# inputmgr.net
KiCad netlist of a schematic drawn in EAGLE
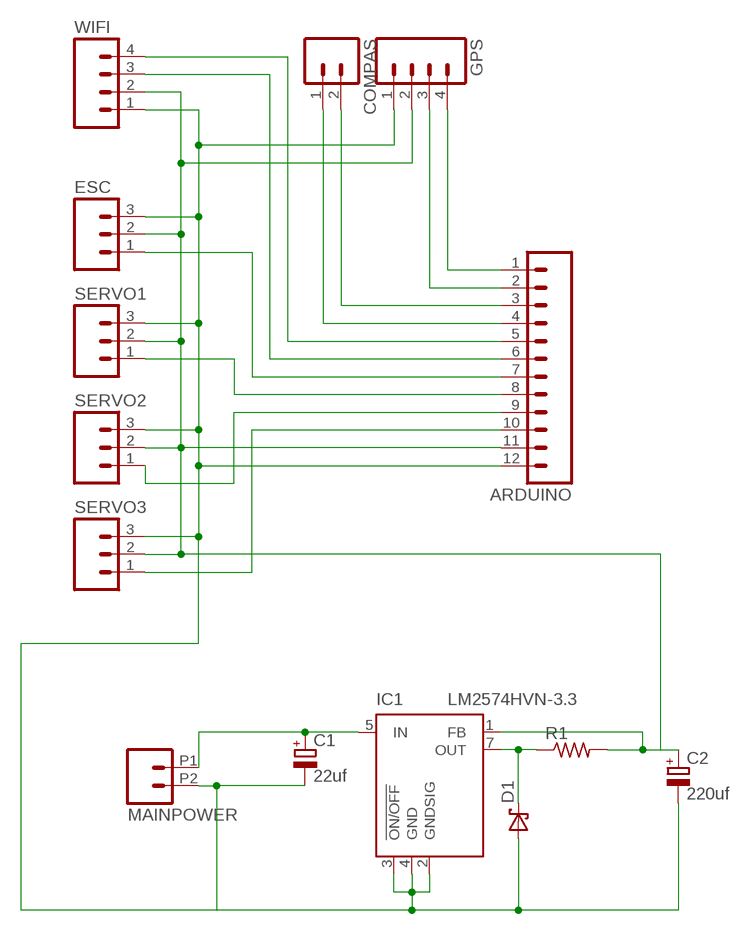
[diagram p0: schematic, sheet 1]

(export (version "E")
  (design (tool "Eeschema 10.0.6"))
  (components
    (comp (ref "ARDUINO")
      (value "M12PTH")
      (footprint "eagle-import:1X12")
      (libsource (lib "eagle-import") (part "M12PTH"))
    )
    (comp (ref "C1")
      (value "22uf")
      (footprint "eagle-import:E2,5-6")
      (libsource (lib "eagle-import") (part "CPOL-EUE2.5-6"))
    )
    (comp (ref "C2")
      (value "220uf")
      (footprint "eagle-import:E2,5-6")
      (libsource (lib "eagle-import") (part "CPOL-EUE2.5-6"))
    )
    (comp (ref "COMPAS")
      (value "M02PTH")
      (footprint "eagle-import:1X02")
      (libsource (lib "eagle-import") (part "M02PTH"))
    )
    (comp (ref "D1")
      (value "DS_E2L")
      (footprint "eagle-import:E2LINE")
      (libsource (lib "eagle-import") (part "DS_E2L"))
    )
    (comp (ref "ESC")
      (value "M03PTH")
      (footprint "eagle-import:1X03")
      (libsource (lib "eagle-import") (part "M03PTH"))
    )
    (comp (ref "GPS")
      (value "M04PTH")
      (footprint "eagle-import:1X04")
      (libsource (lib "eagle-import") (part "M04PTH"))
    )
    (comp (ref "IC1")
      (value "LM2574HVN-3.3")
      (footprint "eagle-import:DIL08")
      (libsource (lib "eagle-import") (part "LM2574?-HVN3.3"))
    )
    (comp (ref "MAINPOWER")
      (value "M022.54MM_SCREWTERM")
      (footprint "eagle-import:1X02_2.54_SCREWTERM")
      (libsource (lib "eagle-import") (part "M022.54MM_SCREWTERM"))
    )
    (comp (ref "R1")
      (value "R-US_0207/7")
      (footprint "eagle-import:0207_7")
      (libsource (lib "eagle-import") (part "R-US_0207/7"))
    )
    (comp (ref "SERVO1")
      (value "M03PTH")
      (footprint "eagle-import:1X03")
      (libsource (lib "eagle-import") (part "M03PTH"))
    )
    (comp (ref "SERVO2")
      (value "M03PTH")
      (footprint "eagle-import:1X03")
      (libsource (lib "eagle-import") (part "M03PTH"))
    )
    (comp (ref "SERVO3")
      (value "M03PTH")
      (footprint "eagle-import:1X03")
      (libsource (lib "eagle-import") (part "M03PTH"))
    )
    (comp (ref "WIFI")
      (value "M04LOCK")
      (footprint "eagle-import:1X04_LOCK")
      (libsource (lib "eagle-import") (part "M04LOCK"))
    )
  )
  (nets
    (net (code "1") (name "Net-(ARDUINO-Pad1)") (class "Default")
      (node (ref "ARDUINO") (pin "1") (pinfunction "1_1") (pintype "passive"))
      (node (ref "GPS") (pin "4") (pinfunction "4_4") (pintype "passive"))
    )
    (net (code "2") (name "Net-(ARDUINO-Pad2)") (class "Default")
      (node (ref "ARDUINO") (pin "2") (pinfunction "2_2") (pintype "passive"))
      (node (ref "GPS") (pin "3") (pinfunction "3_3") (pintype "passive"))
    )
    (net (code "3") (name "Net-(ARDUINO-Pad3)") (class "Default")
      (node (ref "ARDUINO") (pin "3") (pinfunction "3_3") (pintype "passive"))
      (node (ref "COMPAS") (pin "2") (pinfunction "2_2") (pintype "passive"))
    )
    (net (code "4") (name "Net-(ARDUINO-Pad4)") (class "Default")
      (node (ref "ARDUINO") (pin "4") (pinfunction "4_4") (pintype "passive"))
      (node (ref "COMPAS") (pin "1") (pinfunction "1_1") (pintype "passive"))
    )
    (net (code "5") (name "Net-(ARDUINO-Pad5)") (class "Default")
      (node (ref "ARDUINO") (pin "5") (pinfunction "5_5") (pintype "passive"))
      (node (ref "WIFI") (pin "4") (pinfunction "4_4") (pintype "passive"))
    )
    (net (code "6") (name "Net-(ARDUINO-Pad6)") (class "Default")
      (node (ref "ARDUINO") (pin "6") (pinfunction "6_6") (pintype "passive"))
      (node (ref "WIFI") (pin "3") (pinfunction "3_3") (pintype "passive"))
    )
    (net (code "7") (name "Net-(ARDUINO-Pad7)") (class "Default")
      (node (ref "ARDUINO") (pin "7") (pinfunction "7_7") (pintype "passive"))
      (node (ref "ESC") (pin "1") (pinfunction "1_1") (pintype "passive"))
    )
    (net (code "8") (name "Net-(ARDUINO-Pad8)") (class "Default")
      (node (ref "ARDUINO") (pin "8") (pinfunction "8_8") (pintype "passive"))
      (node (ref "SERVO1") (pin "1") (pinfunction "1_1") (pintype "passive"))
    )
    (net (code "9") (name "Net-(ARDUINO-Pad9)") (class "Default")
      (node (ref "ARDUINO") (pin "9") (pinfunction "9_9") (pintype "passive"))
      (node (ref "SERVO2") (pin "1") (pinfunction "1_1") (pintype "passive"))
    )
    (net (code "10") (name "Net-(ARDUINO-Pad10)") (class "Default")
      (node (ref "ARDUINO") (pin "10") (pinfunction "10_10") (pintype "passive"))
      (node (ref "SERVO3") (pin "1") (pinfunction "1_1") (pintype "passive"))
    )
    (net (code "11") (name "Net-(D1-A)") (class "Default")
      (node (ref "ARDUINO") (pin "12") (pinfunction "12_12") (pintype "passive"))
      (node (ref "C1") (pin "-") (pinfunction "-_-") (pintype "passive"))
      (node (ref "C2") (pin "-") (pinfunction "-_-") (pintype "passive"))
      (node (ref "D1") (pin "2") (pinfunction "A_2") (pintype "passive"))
      (node (ref "ESC") (pin "3") (pinfunction "3_3") (pintype "passive"))
      (node (ref "GPS") (pin "1") (pinfunction "1_1") (pintype "passive"))
      (node (ref "IC1") (pin "2") (pinfunction "GNDSIG_2") (pintype "input"))
      (node (ref "IC1") (pin "3") (pinfunction "~{ON/OFF}_3") (pintype "input"))
      (node (ref "IC1") (pin "4") (pinfunction "GND_4") (pintype "power_in"))
      (node (ref "MAINPOWER") (pin "P2") (pinfunction "2_P2") (pintype "passive"))
      (node (ref "SERVO1") (pin "3") (pinfunction "3_3") (pintype "passive"))
      (node (ref "SERVO2") (pin "3") (pinfunction "3_3") (pintype "passive"))
      (node (ref "SERVO3") (pin "3") (pinfunction "3_3") (pintype "passive"))
      (node (ref "WIFI") (pin "1") (pinfunction "1_1") (pintype "passive"))
    )
    (net (code "12") (name "Net-(D1-K)") (class "Default")
      (node (ref "D1") (pin "1") (pinfunction "K_1") (pintype "passive"))
      (node (ref "IC1") (pin "7") (pinfunction "OUT_7") (pintype "passive"))
      (node (ref "R1") (pin "1") (pinfunction "1_1") (pintype "passive"))
    )
    (net (code "13") (name "Net-(IC1-FB)") (class "Default")
      (node (ref "ARDUINO") (pin "11") (pinfunction "11_11") (pintype "passive"))
      (node (ref "C2") (pin "+") (pinfunction "+_+") (pintype "passive"))
      (node (ref "ESC") (pin "2") (pinfunction "2_2") (pintype "passive"))
      (node (ref "GPS") (pin "2") (pinfunction "2_2") (pintype "passive"))
      (node (ref "IC1") (pin "1") (pinfunction "FB_1") (pintype "input"))
      (node (ref "R1") (pin "2") (pinfunction "2_2") (pintype "passive"))
      (node (ref "SERVO1") (pin "2") (pinfunction "2_2") (pintype "passive"))
      (node (ref "SERVO2") (pin "2") (pinfunction "2_2") (pintype "passive"))
      (node (ref "SERVO3") (pin "2") (pinfunction "2_2") (pintype "passive"))
      (node (ref "WIFI") (pin "2") (pinfunction "2_2") (pintype "passive"))
    )
    (net (code "14") (name "Net-(IC1-IN)") (class "Default")
      (node (ref "C1") (pin "+") (pinfunction "+_+") (pintype "passive"))
      (node (ref "IC1") (pin "5") (pinfunction "IN_5") (pintype "input"))
      (node (ref "MAINPOWER") (pin "P1") (pinfunction "1_P1") (pintype "passive"))
    )
  )
)
